# IADC_PCB_SCH.net
KiCad netlist of a schematic drawn in Altium Designer
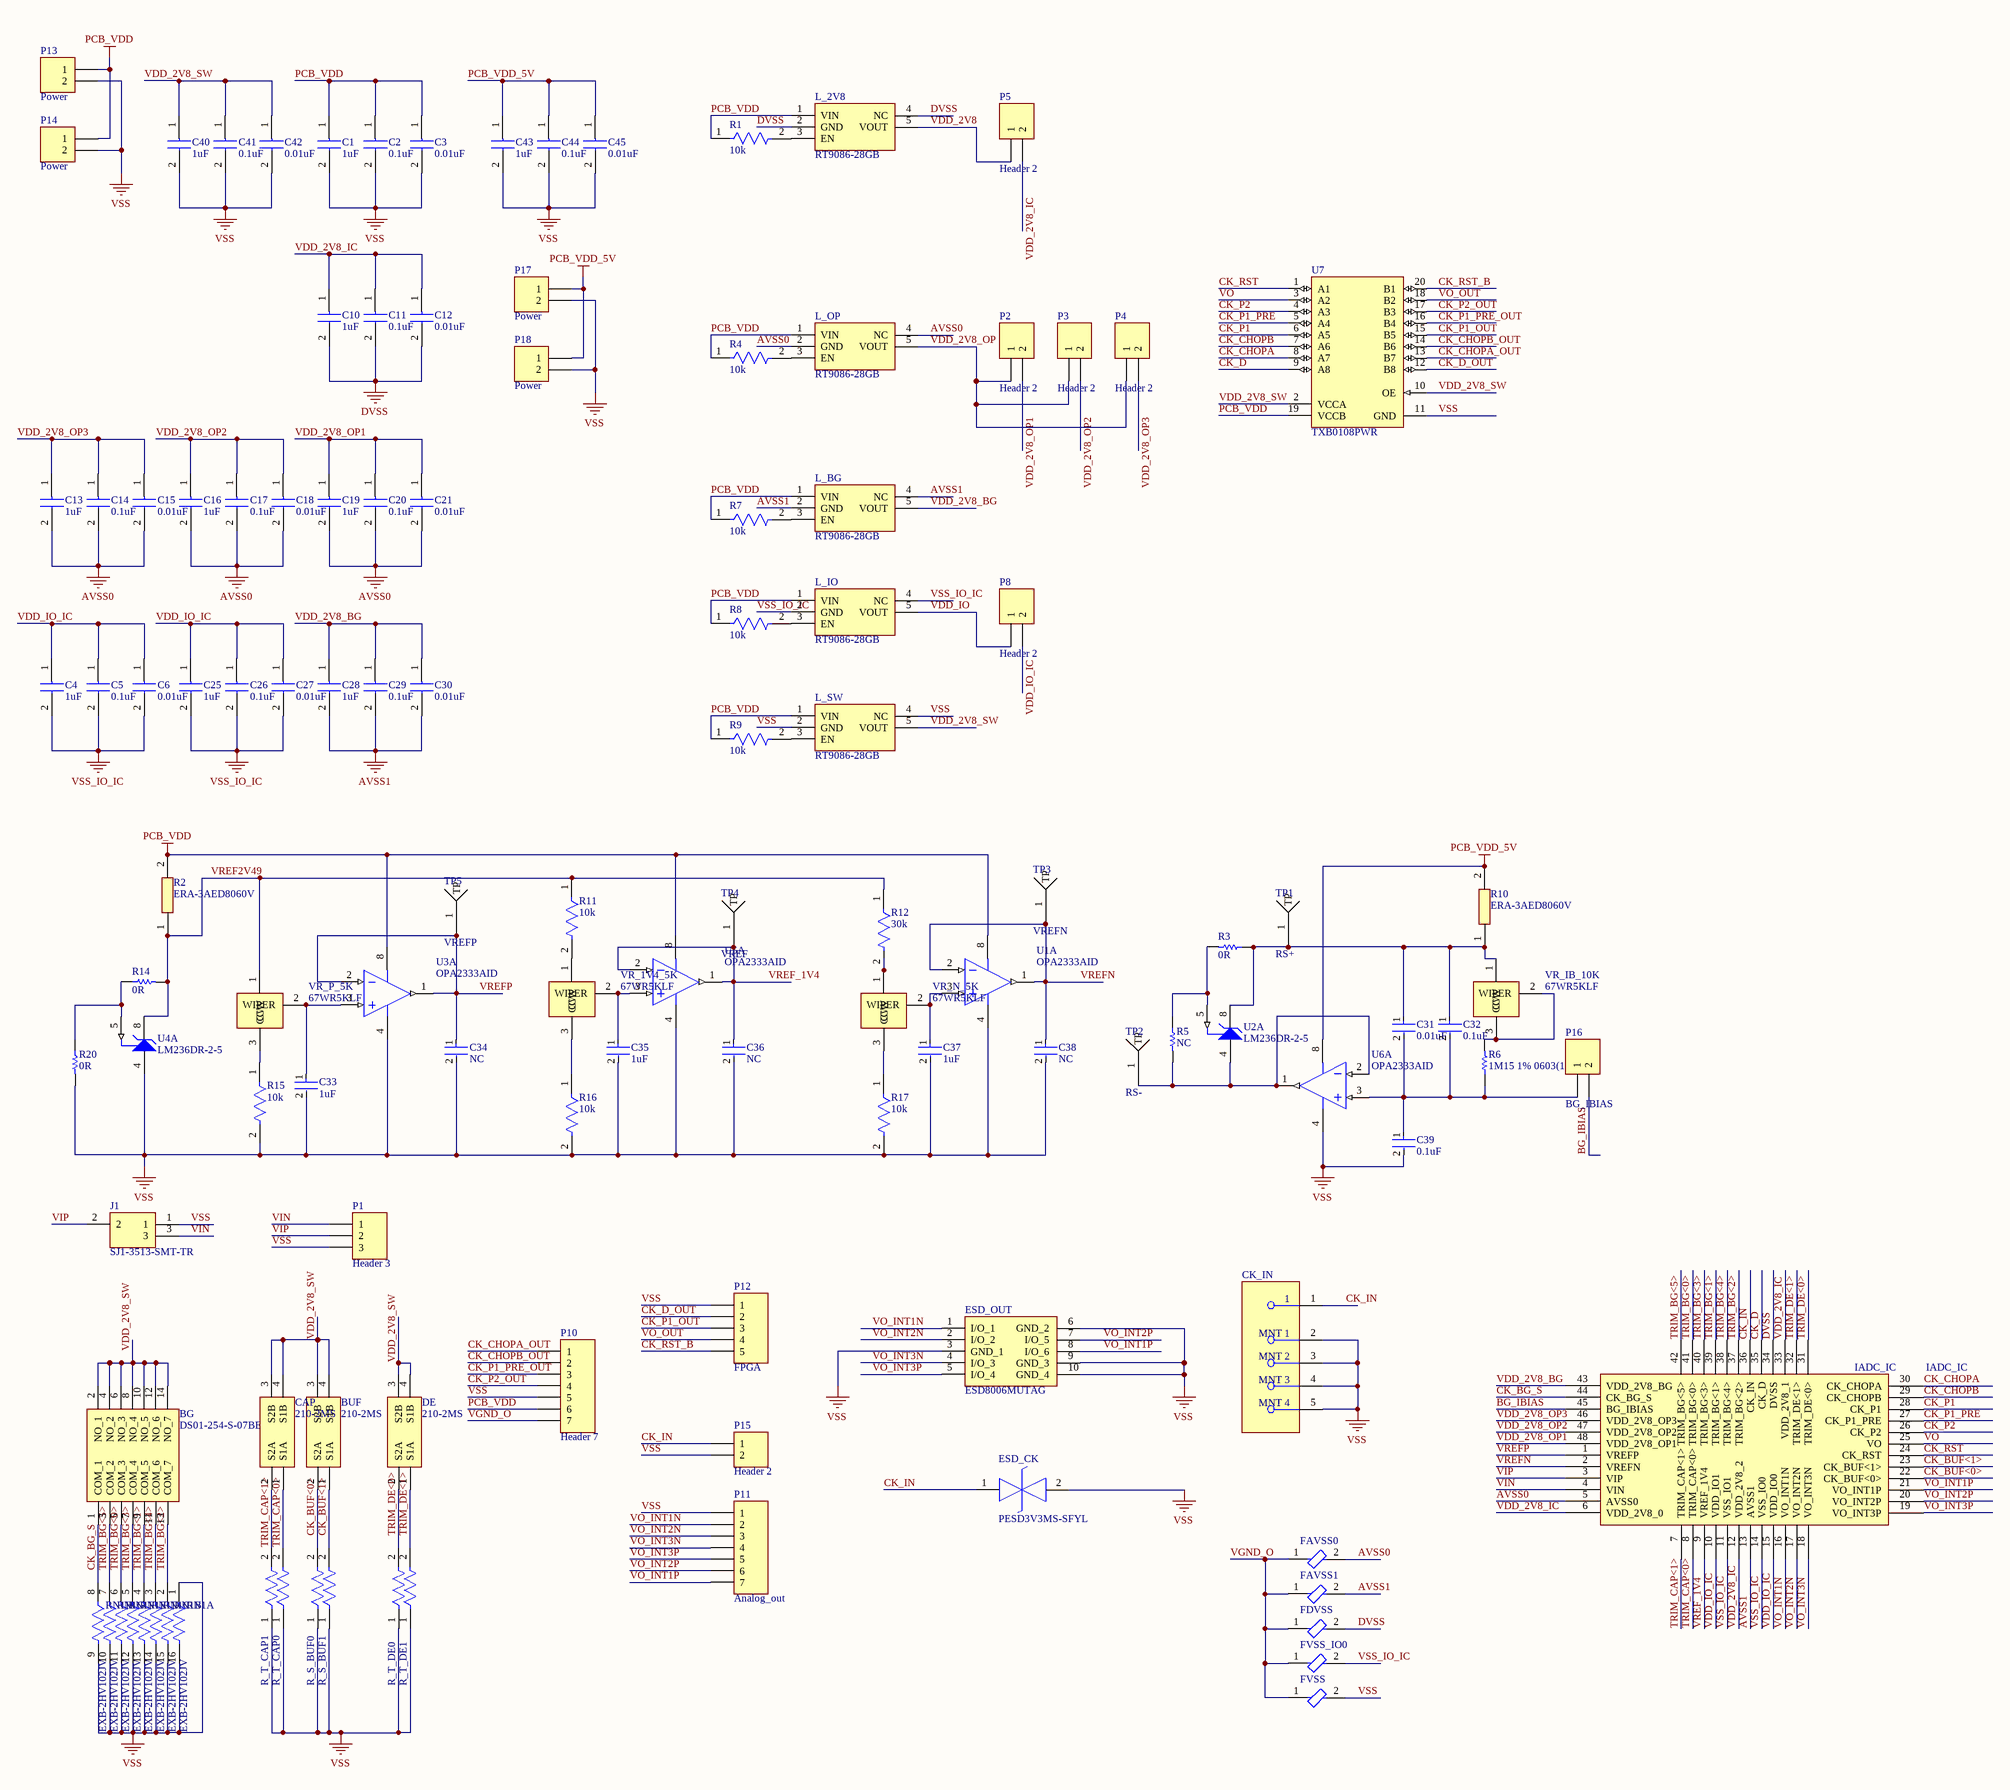
[diagram p0: IADC_PCB_SCH.SchDoc]

(export (version "E")
  (design (tool "Eeschema 10.0.6"))
  (components
    (comp (ref "BG")
      (value "DS01-254-S-07BE")
      (footprint "SamacSys:DS01254S07BE")
      (description "Switch")
      (fields (field (name "MOUSER PART NUMBER") "490-DS01-254-S-07BE"))
      (libsource (lib "Schlib2") (part "DS01-254-S-07BE"))
    )
    (comp (ref "BUF")
      (value "210-2MS")
      (footprint "SamacSys:DIP775W63P254L655H458Q4N")
      (description "Switch")
      (fields (field (name "MOUSER PART NUMBER") "774-2102MS"))
      (libsource (lib "Schlib2") (part "210-2MS"))
    )
    (comp (ref "C1")
      (value "1uF")
      (footprint "SamacSys:CAPC1608X95N")
      (description "多層陶瓷電容器MLCC - SMD/SMT 50V 1uF X7R 0603 10% HI CV")
      (fields
        (field (name "MANUFACTURER_PART_NUMBER") "CC0603KRX7R9BB105")
        (field (name "MOUSER PART NUMBER") "603-CC603KRX7R9BB105")
      )
      (libsource (lib "Schlib2") (part "CC0603KRX7R9BB105"))
    )
    (comp (ref "C2")
      (value "0.1uF")
      (footprint "SamacSys:CAPC1608X90N")
      (description "多層陶瓷電容器MLCC - SMD/SMT 25 V 0.1uF X7R 0603 10%")
      (fields
        (field (name "MANUFACTURER_PART_NUMBER") "CC0603KRX7R8BB104")
        (field (name "MOUSER PART NUMBER") "603-CC603KRX7R8BB104")
      )
      (libsource (lib "Schlib2") (part "CC0603KRX7R8BB104"))
    )
    (comp (ref "C3")
      (value "0.01uF")
      (footprint "SamacSys:CAPC1608X95N")
      (description "多層陶瓷電容器MLCC - SMD/SMT 25V 0.01uF X7R 0603 10%")
      (fields
        (field (name "MANUFACTURER_PART_NUMBER") "CC0603KRX7R9BB105")
        (field (name "MOUSER PART NUMBER") "603-CC603KRX7R9BB105")
      )
      (libsource (lib "Schlib2") (part "CC0603KRX7R9BB105_1"))
    )
    (comp (ref "C4")
      (value "1uF")
      (footprint "SamacSys:CAPC1608X95N")
      (description "多層陶瓷電容器MLCC - SMD/SMT 50V 1uF X7R 0603 10% HI CV")
      (fields
        (field (name "MANUFACTURER_PART_NUMBER") "CC0603KRX7R9BB105")
        (field (name "MOUSER PART NUMBER") "603-CC603KRX7R9BB105")
      )
      (libsource (lib "Schlib2") (part "CC0603KRX7R9BB105"))
    )
    (comp (ref "C5")
      (value "0.1uF")
      (footprint "SamacSys:CAPC1608X90N")
      (description "多層陶瓷電容器MLCC - SMD/SMT 25 V 0.1uF X7R 0603 10%")
      (fields
        (field (name "MANUFACTURER_PART_NUMBER") "CC0603KRX7R8BB104")
        (field (name "MOUSER PART NUMBER") "603-CC603KRX7R8BB104")
      )
      (libsource (lib "Schlib2") (part "CC0603KRX7R8BB104"))
    )
    (comp (ref "C6")
      (value "0.01uF")
      (footprint "SamacSys:CAPC1608X95N")
      (description "多層陶瓷電容器MLCC - SMD/SMT 25V 0.01uF X7R 0603 10%")
      (fields
        (field (name "MANUFACTURER_PART_NUMBER") "CC0603KRX7R9BB105")
        (field (name "MOUSER PART NUMBER") "603-CC603KRX7R9BB105")
      )
      (libsource (lib "Schlib2") (part "CC0603KRX7R9BB105_1"))
    )
    (comp (ref "C10")
      (value "1uF")
      (footprint "SamacSys:CAPC1608X95N")
      (description "多層陶瓷電容器MLCC - SMD/SMT 50V 1uF X7R 0603 10% HI CV")
      (fields
        (field (name "MANUFACTURER_PART_NUMBER") "CC0603KRX7R9BB105")
        (field (name "MOUSER PART NUMBER") "603-CC603KRX7R9BB105")
      )
      (libsource (lib "Schlib2") (part "CC0603KRX7R9BB105"))
    )
    (comp (ref "C11")
      (value "0.1uF")
      (footprint "SamacSys:CAPC1608X90N")
      (description "多層陶瓷電容器MLCC - SMD/SMT 25 V 0.1uF X7R 0603 10%")
      (fields
        (field (name "MANUFACTURER_PART_NUMBER") "CC0603KRX7R8BB104")
        (field (name "MOUSER PART NUMBER") "603-CC603KRX7R8BB104")
      )
      (libsource (lib "Schlib2") (part "CC0603KRX7R8BB104"))
    )
    (comp (ref "C12")
      (value "0.01uF")
      (footprint "SamacSys:CAPC1608X95N")
      (description "多層陶瓷電容器MLCC - SMD/SMT 25V 0.01uF X7R 0603 10%")
      (fields
        (field (name "MANUFACTURER_PART_NUMBER") "CC0603KRX7R9BB105")
        (field (name "MOUSER PART NUMBER") "603-CC603KRX7R9BB105")
      )
      (libsource (lib "Schlib2") (part "CC0603KRX7R9BB105_1"))
    )
    (comp (ref "C13")
      (value "1uF")
      (footprint "SamacSys:CAPC1608X95N")
      (description "多層陶瓷電容器MLCC - SMD/SMT 50V 1uF X7R 0603 10% HI CV")
      (fields
        (field (name "MANUFACTURER_PART_NUMBER") "CC0603KRX7R9BB105")
        (field (name "MOUSER PART NUMBER") "603-CC603KRX7R9BB105")
      )
      (libsource (lib "Schlib2") (part "CC0603KRX7R9BB105"))
    )
    (comp (ref "C14")
      (value "0.1uF")
      (footprint "SamacSys:CAPC1608X90N")
      (description "多層陶瓷電容器MLCC - SMD/SMT 25 V 0.1uF X7R 0603 10%")
      (fields
        (field (name "MANUFACTURER_PART_NUMBER") "CC0603KRX7R8BB104")
        (field (name "MOUSER PART NUMBER") "603-CC603KRX7R8BB104")
      )
      (libsource (lib "Schlib2") (part "CC0603KRX7R8BB104"))
    )
    (comp (ref "C15")
      (value "0.01uF")
      (footprint "SamacSys:CAPC1608X95N")
      (description "多層陶瓷電容器MLCC - SMD/SMT 25V 0.01uF X7R 0603 10%")
      (fields
        (field (name "MANUFACTURER_PART_NUMBER") "CC0603KRX7R9BB105")
        (field (name "MOUSER PART NUMBER") "603-CC603KRX7R9BB105")
      )
      (libsource (lib "Schlib2") (part "CC0603KRX7R9BB105_1"))
    )
    (comp (ref "C16")
      (value "1uF")
      (footprint "SamacSys:CAPC1608X95N")
      (description "多層陶瓷電容器MLCC - SMD/SMT 50V 1uF X7R 0603 10% HI CV")
      (fields
        (field (name "MANUFACTURER_PART_NUMBER") "CC0603KRX7R9BB105")
        (field (name "MOUSER PART NUMBER") "603-CC603KRX7R9BB105")
      )
      (libsource (lib "Schlib2") (part "CC0603KRX7R9BB105"))
    )
    (comp (ref "C17")
      (value "0.1uF")
      (footprint "SamacSys:CAPC1608X90N")
      (description "多層陶瓷電容器MLCC - SMD/SMT 25 V 0.1uF X7R 0603 10%")
      (fields
        (field (name "MANUFACTURER_PART_NUMBER") "CC0603KRX7R8BB104")
        (field (name "MOUSER PART NUMBER") "603-CC603KRX7R8BB104")
      )
      (libsource (lib "Schlib2") (part "CC0603KRX7R8BB104"))
    )
    (comp (ref "C18")
      (value "0.01uF")
      (footprint "SamacSys:CAPC1608X95N")
      (description "多層陶瓷電容器MLCC - SMD/SMT 25V 0.01uF X7R 0603 10%")
      (fields
        (field (name "MANUFACTURER_PART_NUMBER") "CC0603KRX7R9BB105")
        (field (name "MOUSER PART NUMBER") "603-CC603KRX7R9BB105")
      )
      (libsource (lib "Schlib2") (part "CC0603KRX7R9BB105_1"))
    )
    (comp (ref "C19")
      (value "1uF")
      (footprint "SamacSys:CAPC1608X95N")
      (description "多層陶瓷電容器MLCC - SMD/SMT 50V 1uF X7R 0603 10% HI CV")
      (fields
        (field (name "MANUFACTURER_PART_NUMBER") "CC0603KRX7R9BB105")
        (field (name "MOUSER PART NUMBER") "603-CC603KRX7R9BB105")
      )
      (libsource (lib "Schlib2") (part "CC0603KRX7R9BB105"))
    )
    (comp (ref "C20")
      (value "0.1uF")
      (footprint "SamacSys:CAPC1608X90N")
      (description "多層陶瓷電容器MLCC - SMD/SMT 25 V 0.1uF X7R 0603 10%")
      (fields
        (field (name "MANUFACTURER_PART_NUMBER") "CC0603KRX7R8BB104")
        (field (name "MOUSER PART NUMBER") "603-CC603KRX7R8BB104")
      )
      (libsource (lib "Schlib2") (part "CC0603KRX7R8BB104"))
    )
    (comp (ref "C21")
      (value "0.01uF")
      (footprint "SamacSys:CAPC1608X95N")
      (description "多層陶瓷電容器MLCC - SMD/SMT 25V 0.01uF X7R 0603 10%")
      (fields
        (field (name "MANUFACTURER_PART_NUMBER") "CC0603KRX7R9BB105")
        (field (name "MOUSER PART NUMBER") "603-CC603KRX7R9BB105")
      )
      (libsource (lib "Schlib2") (part "CC0603KRX7R9BB105_1"))
    )
    (comp (ref "C25")
      (value "1uF")
      (footprint "SamacSys:CAPC1608X95N")
      (description "多層陶瓷電容器MLCC - SMD/SMT 50V 1uF X7R 0603 10% HI CV")
      (fields
        (field (name "MANUFACTURER_PART_NUMBER") "CC0603KRX7R9BB105")
        (field (name "MOUSER PART NUMBER") "603-CC603KRX7R9BB105")
      )
      (libsource (lib "Schlib2") (part "CC0603KRX7R9BB105"))
    )
    (comp (ref "C26")
      (value "0.1uF")
      (footprint "SamacSys:CAPC1608X90N")
      (description "多層陶瓷電容器MLCC - SMD/SMT 25 V 0.1uF X7R 0603 10%")
      (fields
        (field (name "MANUFACTURER_PART_NUMBER") "CC0603KRX7R8BB104")
        (field (name "MOUSER PART NUMBER") "603-CC603KRX7R8BB104")
      )
      (libsource (lib "Schlib2") (part "CC0603KRX7R8BB104"))
    )
    (comp (ref "C27")
      (value "0.01uF")
      (footprint "SamacSys:CAPC1608X95N")
      (description "多層陶瓷電容器MLCC - SMD/SMT 25V 0.01uF X7R 0603 10%")
      (fields
        (field (name "MANUFACTURER_PART_NUMBER") "CC0603KRX7R9BB105")
        (field (name "MOUSER PART NUMBER") "603-CC603KRX7R9BB105")
      )
      (libsource (lib "Schlib2") (part "CC0603KRX7R9BB105_1"))
    )
    (comp (ref "C28")
      (value "1uF")
      (footprint "SamacSys:CAPC1608X95N")
      (description "多層陶瓷電容器MLCC - SMD/SMT 50V 1uF X7R 0603 10% HI CV")
      (fields
        (field (name "MANUFACTURER_PART_NUMBER") "CC0603KRX7R9BB105")
        (field (name "MOUSER PART NUMBER") "603-CC603KRX7R9BB105")
      )
      (libsource (lib "Schlib2") (part "CC0603KRX7R9BB105"))
    )
    (comp (ref "C29")
      (value "0.1uF")
      (footprint "SamacSys:CAPC1608X90N")
      (description "多層陶瓷電容器MLCC - SMD/SMT 25 V 0.1uF X7R 0603 10%")
      (fields
        (field (name "MANUFACTURER_PART_NUMBER") "CC0603KRX7R8BB104")
        (field (name "MOUSER PART NUMBER") "603-CC603KRX7R8BB104")
      )
      (libsource (lib "Schlib2") (part "CC0603KRX7R8BB104"))
    )
    (comp (ref "C30")
      (value "0.01uF")
      (footprint "SamacSys:CAPC1608X95N")
      (description "多層陶瓷電容器MLCC - SMD/SMT 25V 0.01uF X7R 0603 10%")
      (fields
        (field (name "MANUFACTURER_PART_NUMBER") "CC0603KRX7R9BB105")
        (field (name "MOUSER PART NUMBER") "603-CC603KRX7R9BB105")
      )
      (libsource (lib "Schlib2") (part "CC0603KRX7R9BB105_1"))
    )
    (comp (ref "C31")
      (value "0.01uF")
      (footprint "FP-CC0603-DA-MFG")
      (description "CAP CER 10000PF 50V X7R 0603")
      (fields (field (name "TOLERANCE") "0.1") (field (name "MANUFACTURER PART NUMBER") "CC0603KRX7R9BB103"))
      (libsource (lib "Altium Content Vault") (part "11868f565c42a9108669ba33697ecf6"))
    )
    (comp (ref "C32")
      (value "0.1uF")
      (footprint "FP-CC0603-DA-MFG")
      (description "CAP CER 0.1UF 50V X7R 0603")
      (fields (field (name "MANUFACTURER") "YAGEO") (field (name "VOLTAGE") "50 V"))
      (libsource (lib "Altium Content Vault") (part "11868f565c42a9108669ba33697ecf6"))
    )
    (comp (ref "C33")
      (value "1uF")
      (footprint "FP-CC0603-DA-MFG")
      (description "CAP CER 1UF 16V X7R 0603")
      (fields (field (name "TOLERANCE") "0.1") (field (name "MANUFACTURER") "YAGEO"))
      (libsource (lib "Altium Content Vault") (part "11868f565c42a9108669ba33697ecf6"))
    )
    (comp (ref "C34")
      (value "NC")
      (footprint "FP-CC0603-DA-MFG")
      (description "CAP CER 1UF 16V X7R 0603")
      (fields (field (name "TOLERANCE") "0.1") (field (name "MANUFACTURER") "YAGEO"))
      (libsource (lib "Altium Content Vault") (part "11868f565c42a9108669ba33697ecf6"))
    )
    (comp (ref "C35")
      (value "1uF")
      (footprint "FP-CC0603-DA-MFG")
      (description "CAP CER 1UF 16V X7R 0603")
      (fields (field (name "TOLERANCE") "0.1") (field (name "MANUFACTURER") "YAGEO"))
      (libsource (lib "Altium Content Vault") (part "11868f565c42a9108669ba33697ecf6"))
    )
    (comp (ref "C36")
      (value "NC")
      (footprint "FP-CC0603-DA-MFG")
      (description "CAP CER 1UF 16V X7R 0603")
      (fields (field (name "TOLERANCE") "0.1") (field (name "MANUFACTURER") "YAGEO"))
      (libsource (lib "Altium Content Vault") (part "11868f565c42a9108669ba33697ecf6"))
    )
    (comp (ref "C37")
      (value "1uF")
      (footprint "FP-CC0603-DA-MFG")
      (description "CAP CER 1UF 16V X7R 0603")
      (fields (field (name "TOLERANCE") "0.1") (field (name "MANUFACTURER") "YAGEO"))
      (libsource (lib "Altium Content Vault") (part "11868f565c42a9108669ba33697ecf6"))
    )
    (comp (ref "C38")
      (value "NC")
      (footprint "FP-CC0603-DA-MFG")
      (description "CAP CER 1UF 16V X7R 0603")
      (fields (field (name "TOLERANCE") "0.1") (field (name "MANUFACTURER") "YAGEO"))
      (libsource (lib "Altium Content Vault") (part "11868f565c42a9108669ba33697ecf6"))
    )
    (comp (ref "C39")
      (value "0.1uF")
      (footprint "FP-CC0603-DA-MFG")
      (description "CAP CER 0.1UF 50V X7R 0603")
      (fields (field (name "MANUFACTURER") "YAGEO") (field (name "VOLTAGE") "50 V"))
      (libsource (lib "Altium Content Vault") (part "11868f565c42a9108669ba33697ecf6"))
    )
    (comp (ref "C40")
      (value "1uF")
      (footprint "SamacSys:CAPC1608X95N")
      (description "多層陶瓷電容器MLCC - SMD/SMT 50V 1uF X7R 0603 10% HI CV")
      (fields
        (field (name "MANUFACTURER_PART_NUMBER") "CC0603KRX7R9BB105")
        (field (name "MOUSER PART NUMBER") "603-CC603KRX7R9BB105")
      )
      (libsource (lib "Schlib2") (part "CC0603KRX7R9BB105"))
    )
    (comp (ref "C41")
      (value "0.1uF")
      (footprint "SamacSys:CAPC1608X90N")
      (description "多層陶瓷電容器MLCC - SMD/SMT 25 V 0.1uF X7R 0603 10%")
      (fields
        (field (name "MANUFACTURER_PART_NUMBER") "CC0603KRX7R8BB104")
        (field (name "MOUSER PART NUMBER") "603-CC603KRX7R8BB104")
      )
      (libsource (lib "Schlib2") (part "CC0603KRX7R8BB104"))
    )
    (comp (ref "C42")
      (value "0.01uF")
      (footprint "SamacSys:CAPC1608X95N")
      (description "多層陶瓷電容器MLCC - SMD/SMT 25V 0.01uF X7R 0603 10%")
      (fields
        (field (name "MANUFACTURER_PART_NUMBER") "CC0603KRX7R9BB105")
        (field (name "MOUSER PART NUMBER") "603-CC603KRX7R9BB105")
      )
      (libsource (lib "Schlib2") (part "CC0603KRX7R9BB105_1"))
    )
    (comp (ref "C43")
      (value "1uF")
      (footprint "SamacSys:CAPC1608X95N")
      (description "多層陶瓷電容器MLCC - SMD/SMT 50V 1uF X7R 0603 10% HI CV")
      (fields
        (field (name "MANUFACTURER_PART_NUMBER") "CC0603KRX7R9BB105")
        (field (name "MOUSER PART NUMBER") "603-CC603KRX7R9BB105")
      )
      (libsource (lib "Schlib2") (part "CC0603KRX7R9BB105"))
    )
    (comp (ref "C44")
      (value "0.1uF")
      (footprint "SamacSys:CAPC1608X90N")
      (description "多層陶瓷電容器MLCC - SMD/SMT 25 V 0.1uF X7R 0603 10%")
      (fields
        (field (name "MANUFACTURER_PART_NUMBER") "CC0603KRX7R8BB104")
        (field (name "MOUSER PART NUMBER") "603-CC603KRX7R8BB104")
      )
      (libsource (lib "Schlib2") (part "CC0603KRX7R8BB104"))
    )
    (comp (ref "C45")
      (value "0.01uF")
      (footprint "SamacSys:CAPC1608X95N")
      (description "多層陶瓷電容器MLCC - SMD/SMT 25V 0.01uF X7R 0603 10%")
      (fields
        (field (name "MANUFACTURER_PART_NUMBER") "CC0603KRX7R9BB105")
        (field (name "MOUSER PART NUMBER") "603-CC603KRX7R9BB105")
      )
      (libsource (lib "Schlib2") (part "CC0603KRX7R9BB105_1"))
    )
    (comp (ref "CAP")
      (value "210-2MS")
      (footprint "SamacSys:DIP775W63P254L655H458Q4N")
      (description "Switch")
      (fields (field (name "MOUSER PART NUMBER") "774-2102MS"))
      (libsource (lib "Schlib2") (part "210-2MS"))
    )
    (comp (ref "CK_IN")
      (value "221790-1")
      (footprint "FP-221790-1-MFG")
      (description "CONN SMA JACK R/A 50 OHM PCB")
      (fields
        (field (name "OCTOPART") "https://octopart.com/2217901-te+connectivity+%2F+amp-3339836")
        (field (name "MANUFACTURER") "TE Connectivity / AMP")
      )
      (libsource (lib "Altium Content Vault") (part "c65b8a639cdaef1819ea20b5466f8fa"))
    )
    (comp (ref "DE")
      (value "210-2MS")
      (footprint "SamacSys:DIP775W63P254L655H458Q4N")
      (description "Switch")
      (fields (field (name "MOUSER PART NUMBER") "774-2102MS"))
      (libsource (lib "Schlib2") (part "210-2MS"))
    )
    (comp (ref "ESD_CK")
      (value "PESD3V3MS-SFYL")
      (footprint "SamacSys:PMEG3005AESFYL")
      (description "Diode ESD (Bi-directional)")
      (fields (field (name "MOUSER PART NUMBER") "771-PESD3V3MS-SFYL"))
      (libsource (lib "Schlib2") (part "PESD3V3MS-SFYL"))
    )
    (comp (ref "ESD_OUT")
      (value "ESD8006MUTAG")
      (footprint "SamacSys:ESD8006MUTAG")
      (description "Integrated Circuit")
      (fields (field (name "MOUSER PART NUMBER") "863-ESD8006MUTAG"))
      (libsource (lib "Schlib2") (part "ESD8006MUTAG"))
    )
    (comp (ref "FAVSS0")
      (value "742792609")
      (footprint "FP-742792609-MFG")
      (description "FERRITE BEAD 30 OHM 0603 1LN")
      (fields (field (name "TOLERANCE") "25%"))
      (libsource (lib "Altium Content Vault") (part "5f30dd21d616792df468990f7003faa"))
    )
    (comp (ref "FAVSS1")
      (value "742792609")
      (footprint "FP-742792609-MFG")
      (description "FERRITE BEAD 30 OHM 0603 1LN")
      (fields (field (name "TOLERANCE") "25%"))
      (libsource (lib "Altium Content Vault") (part "5f30dd21d616792df468990f7003faa"))
    )
    (comp (ref "FDVSS")
      (value "742792609")
      (footprint "FP-742792609-MFG")
      (description "FERRITE BEAD 30 OHM 0603 1LN")
      (fields (field (name "TOLERANCE") "25%"))
      (libsource (lib "Altium Content Vault") (part "5f30dd21d616792df468990f7003faa"))
    )
    (comp (ref "FVSS")
      (value "742792609")
      (footprint "FP-742792609-MFG")
      (description "FERRITE BEAD 30 OHM 0603 1LN")
      (fields (field (name "TOLERANCE") "25%"))
      (libsource (lib "Altium Content Vault") (part "5f30dd21d616792df468990f7003faa"))
    )
    (comp (ref "FVSS_IO0")
      (value "742792609")
      (footprint "FP-742792609-MFG")
      (description "FERRITE BEAD 30 OHM 0603 1LN")
      (fields (field (name "TOLERANCE") "25%"))
      (libsource (lib "Altium Content Vault") (part "5f30dd21d616792df468990f7003faa"))
    )
    (comp (ref "IADC_IC")
      (value "IADC_IC")
      (footprint "PcbLib1:SB48 (DIP48)")
      (libsource (lib "Schlib2") (part "IADC_IC"))
    )
    (comp (ref "J1")
      (value "SJ1-3513-SMT-TR")
      (footprint "SamacSys:SJ13513SMTTR")
      (description "Connector")
      (fields (field (name "MOUSER PART NUMBER") "490-SJ1-3513-SMT-TR"))
      (libsource (lib "Schlib2") (part "SJ1-3513-SMT-TR"))
    )
    (comp (ref "L_2V8")
      (value "RT9086-28GB")
      (footprint "SamacSys:SOT94P279X130-5N")
      (description "Integrated Circuit")
      (libsource (lib "Schlib2") (part "RT9086-28GB"))
    )
    (comp (ref "L_BG")
      (value "RT9086-28GB")
      (footprint "SamacSys:SOT94P279X130-5N")
      (description "Integrated Circuit")
      (libsource (lib "Schlib2") (part "RT9086-28GB"))
    )
    (comp (ref "L_IO")
      (value "RT9086-28GB")
      (footprint "SamacSys:SOT94P279X130-5N")
      (description "Integrated Circuit")
      (libsource (lib "Schlib2") (part "RT9086-28GB"))
    )
    (comp (ref "L_OP")
      (value "RT9086-28GB")
      (footprint "SamacSys:SOT94P279X130-5N")
      (description "Integrated Circuit")
      (libsource (lib "Schlib2") (part "RT9086-28GB"))
    )
    (comp (ref "L_SW")
      (value "RT9086-28GB")
      (footprint "SamacSys:SOT94P279X130-5N")
      (description "Integrated Circuit")
      (libsource (lib "Schlib2") (part "RT9086-28GB"))
    )
    (comp (ref "P1")
      (value "Header 3")
      (footprint "HDR1X3")
      (description "Header, 3-Pin")
      (fields (field (name "PUBLISHER") "Altium Limited"))
      (libsource (lib "Miscellaneous Connectors") (part "Header 3"))
    )
    (comp (ref "P2")
      (value "Header 2")
      (footprint "HDR1X2")
      (description "Header, 2-Pin")
      (fields (field (name "PUBLISHER") "Altium Limited"))
      (libsource (lib "") (part "Header 2_1"))
    )
    (comp (ref "P3")
      (value "Header 2")
      (footprint "HDR1X2")
      (description "Header, 2-Pin")
      (fields (field (name "PUBLISHER") "Altium Limited"))
      (libsource (lib "") (part "Header 2_1"))
    )
    (comp (ref "P4")
      (value "Header 2")
      (footprint "HDR1X2")
      (description "Header, 2-Pin")
      (fields (field (name "PUBLISHER") "Altium Limited"))
      (libsource (lib "") (part "Header 2_1"))
    )
    (comp (ref "P5")
      (value "Header 2")
      (footprint "HDR1X2")
      (description "Header, 2-Pin")
      (fields (field (name "PUBLISHER") "Altium Limited"))
      (libsource (lib "") (part "Header 2_1"))
    )
    (comp (ref "P8")
      (value "Header 2")
      (footprint "HDR1X2")
      (description "Header, 2-Pin")
      (fields (field (name "PUBLISHER") "Altium Limited"))
      (libsource (lib "") (part "Header 2_1"))
    )
    (comp (ref "P10")
      (value "Header 7")
      (footprint "HDR1X7")
      (description "Header, 7-Pin")
      (fields (field (name "PUBLISHER") "Altium Limited"))
      (libsource (lib "Miscellaneous Connectors") (part "Header 7"))
    )
    (comp (ref "P11")
      (value "Analog_out")
      (footprint "HDR1X7")
      (description "Header, 7-Pin")
      (fields (field (name "PUBLISHER") "Altium Limited"))
      (libsource (lib "Miscellaneous Connectors") (part "Header 7"))
    )
    (comp (ref "P12")
      (value "FPGA")
      (footprint "HDR1X5")
      (description "Header, 5-Pin")
      (fields (field (name "PUBLISHER") "Altium Limited"))
      (libsource (lib "Miscellaneous Connectors") (part "Header 5"))
    )
    (comp (ref "P13")
      (value "Power")
      (footprint "HDR1X2")
      (description "Header, 2-Pin")
      (fields (field (name "PUBLISHER") "Altium Limited"))
      (libsource (lib "") (part "Header 2_2"))
    )
    (comp (ref "P14")
      (value "Power")
      (footprint "HDR1X2")
      (description "Header, 2-Pin")
      (fields (field (name "PUBLISHER") "Altium Limited"))
      (libsource (lib "") (part "Header 2_2"))
    )
    (comp (ref "P15")
      (value "Header 2")
      (footprint "HDR1X2")
      (description "Header, 2-Pin")
      (fields (field (name "PUBLISHER") "Altium Limited"))
      (libsource (lib "Miscellaneous Connectors") (part "Header 2"))
    )
    (comp (ref "P16")
      (value "BG_IBIAS")
      (footprint "HDR1X2")
      (description "Header, 2-Pin")
      (fields (field (name "PUBLISHER") "Altium Limited"))
      (libsource (lib "") (part "Header 2_1"))
    )
    (comp (ref "P17")
      (value "Power")
      (footprint "HDR1X2")
      (description "Header, 2-Pin")
      (fields (field (name "PUBLISHER") "Altium Limited"))
      (libsource (lib "") (part "Header 2_2"))
    )
    (comp (ref "P18")
      (value "Power")
      (footprint "HDR1X2")
      (description "Header, 2-Pin")
      (fields (field (name "PUBLISHER") "Altium Limited"))
      (libsource (lib "") (part "Header 2_2"))
    )
    (comp (ref "R1")
      (value "10k")
      (footprint "FP-RC0603-0_55-IPC_C")
      (description "RES 10K OHM 1% 1/10W 0603")
      (fields (field (name "TOLERANCE") "1%"))
      (libsource (lib "Altium Content Vault") (part "1029c3af85768c4190bb7ad29bc67b5"))
    )
    (comp (ref "R2")
      (value "ERA-3AED8060V")
      (footprint "SamacSys:ERA3AEB101V")
      (description "Resistor")
      (fields (field (name "MOUSER PART NUMBER") "667-ERA-3AED8060V"))
      (libsource (lib "Schlib2") (part "ERA-3AED8060V"))
    )
    (comp (ref "R3")
      (value "0R")
      (footprint "RESC1608X55X25ML10T15")
      (description "Chip Resistor, 0 Ohm, +/- 5%, 0.1 W, -55 to 155 degC, 0603 (1608 Metric), RoHS, Tape and Reel")
      (fields (field (name "TOLERANCE") "5%") (field (name "MANUFACTURER") "Yageo"))
      (libsource (lib "Altium Content Vault") (part "RES-2"))
    )
    (comp (ref "R4")
      (value "10k")
      (footprint "FP-RC0603-0_55-IPC_C")
      (description "RES 10K OHM 1% 1/10W 0603")
      (fields (field (name "TOLERANCE") "1%"))
      (libsource (lib "Altium Content Vault") (part "1029c3af85768c4190bb7ad29bc67b5"))
    )
    (comp (ref "R5")
      (value "NC")
      (footprint "RESC1608X55X25ML10T15")
      (description "Chip Resistor, 0 Ohm, +/- 5%, 0.1 W, -55 to 155 degC, 0603 (1608 Metric), RoHS, Tape and Reel")
      (fields (field (name "TOLERANCE") "5%") (field (name "MANUFACTURER") "Yageo"))
      (libsource (lib "Altium Content Vault") (part "RES-2"))
    )
    (comp (ref "R6")
      (value "1M15 1% 0603(1608)")
      (footprint "RESC0603(1608)_N")
      (description "1M15 0.1W 1% 0603 (1608 Metric)  SMD")
      (fields (field (name "POWER") "0.1 W") (field (name "TOLERANCE") "1 %"))
      (libsource (lib "Altium Content Vault") (part "RES"))
    )
    (comp (ref "R7")
      (value "10k")
      (footprint "FP-RC0603-0_55-IPC_C")
      (description "RES 10K OHM 1% 1/10W 0603")
      (fields (field (name "TOLERANCE") "1%"))
      (libsource (lib "Altium Content Vault") (part "1029c3af85768c4190bb7ad29bc67b5"))
    )
    (comp (ref "R8")
      (value "10k")
      (footprint "FP-RC0603-0_55-IPC_C")
      (description "RES 10K OHM 1% 1/10W 0603")
      (fields (field (name "TOLERANCE") "1%"))
      (libsource (lib "Altium Content Vault") (part "1029c3af85768c4190bb7ad29bc67b5"))
    )
    (comp (ref "R9")
      (value "10k")
      (footprint "FP-RC0603-0_55-IPC_C")
      (description "RES 10K OHM 1% 1/10W 0603")
      (fields (field (name "TOLERANCE") "1%"))
      (libsource (lib "Altium Content Vault") (part "1029c3af85768c4190bb7ad29bc67b5"))
    )
    (comp (ref "R10")
      (value "ERA-3AED8060V")
      (footprint "SamacSys:ERA3AEB101V")
      (description "Resistor")
      (fields (field (name "MOUSER PART NUMBER") "667-ERA-3AED8060V"))
      (libsource (lib "Schlib2") (part "ERA-3AED8060V"))
    )
    (comp (ref "R11")
      (value "10k")
      (footprint "FP-RC0603-0_55-MFG")
      (description "RES 10K OHM 1% 1/10W 0603")
      (fields (field (name "TOLERANCE") "1%"))
      (libsource (lib "Altium Content Vault") (part "1029c3af85768c4190bb7ad29bc67b5"))
    )
    (comp (ref "R12")
      (value "30k")
      (footprint "FP-RC0603-0_55-MFG")
      (description "RES 10K OHM 1% 1/10W 0603")
      (fields (field (name "TOLERANCE") "1%"))
      (libsource (lib "Altium Content Vault") (part "1029c3af85768c4190bb7ad29bc67b5"))
    )
    (comp (ref "R14")
      (value "0R")
      (footprint "RESC1608X55X25ML10T15")
      (description "Chip Resistor, 0 Ohm, +/- 5%, 0.1 W, -55 to 155 degC, 0603 (1608 Metric), RoHS, Tape and Reel")
      (fields (field (name "TOLERANCE") "5%") (field (name "MANUFACTURER") "Yageo"))
      (libsource (lib "Altium Content Vault") (part "RES-2"))
    )
    (comp (ref "R15")
      (value "10k")
      (footprint "FP-RC0603-0_55-MFG")
      (description "RES 10K OHM 1% 1/10W 0603")
      (fields (field (name "TOLERANCE") "1%"))
      (libsource (lib "Altium Content Vault") (part "1029c3af85768c4190bb7ad29bc67b5"))
    )
    (comp (ref "R16")
      (value "10k")
      (footprint "FP-RC0603-0_55-MFG")
      (description "RES 10K OHM 1% 1/10W 0603")
      (fields (field (name "TOLERANCE") "1%"))
      (libsource (lib "Altium Content Vault") (part "1029c3af85768c4190bb7ad29bc67b5"))
    )
    (comp (ref "R17")
      (value "10k")
      (footprint "FP-RC0603-0_55-MFG")
      (description "RES 10K OHM 1% 1/10W 0603")
      (fields (field (name "TOLERANCE") "1%"))
      (libsource (lib "Altium Content Vault") (part "1029c3af85768c4190bb7ad29bc67b5"))
    )
    (comp (ref "R20")
      (value "0R")
      (footprint "RESC1608X55X25ML10T15")
      (description "Chip Resistor, 0 Ohm, +/- 5%, 0.1 W, -55 to 155 degC, 0603 (1608 Metric), RoHS, Tape and Reel")
      (fields (field (name "TOLERANCE") "5%") (field (name "MANUFACTURER") "Yageo"))
      (libsource (lib "Altium Content Vault") (part "RES-2"))
    )
    (comp (ref "RN1")
      (value "EXB-2HV102JV")
      (footprint "FP-EXB2HV-MFG")
      (description "RES ARRAY 8 RES 1K OHM 1506")
      (fields
        (field (name "MANUFACTURER") "Panasonic")
        (field (name "OCTOPART") "https://octopart.com/exb-2hv102jv-panasonic-55561305")
      )
      (libsource (lib "Altium Content Vault") (part "eca46332945381b58ca122c3d0818be"))
    )
    (comp (ref "R_S_BUF0")
      (value "RT0603BRD071KL")
      (footprint "FP-RT0603-MFG")
      (description "RES SMD 1K OHM 0.1% 1/10W 0603")
      (fields (field (name "MANUFACTURER") "Yageo") (field (name "TOLERANCE") "0.1%"))
      (libsource (lib "Altium Content Vault") (part "1029c3af85768c4190bb7ad29bc67b5"))
    )
    (comp (ref "R_S_BUF1")
      (value "RT0603BRD071KL")
      (footprint "FP-RT0603-MFG")
      (description "RES SMD 1K OHM 0.1% 1/10W 0603")
      (fields (field (name "MANUFACTURER") "Yageo") (field (name "TOLERANCE") "0.1%"))
      (libsource (lib "Altium Content Vault") (part "1029c3af85768c4190bb7ad29bc67b5"))
    )
    (comp (ref "R_T_CAP0")
      (value "RT0603BRD071KL")
      (footprint "FP-RT0603-MFG")
      (description "RES SMD 1K OHM 0.1% 1/10W 0603")
      (fields (field (name "MANUFACTURER") "Yageo") (field (name "TOLERANCE") "0.1%"))
      (libsource (lib "Altium Content Vault") (part "1029c3af85768c4190bb7ad29bc67b5"))
    )
    (comp (ref "R_T_CAP1")
      (value "RT0603BRD071KL")
      (footprint "FP-RT0603-MFG")
      (description "RES SMD 1K OHM 0.1% 1/10W 0603")
      (fields (field (name "MANUFACTURER") "Yageo") (field (name "TOLERANCE") "0.1%"))
      (libsource (lib "Altium Content Vault") (part "1029c3af85768c4190bb7ad29bc67b5"))
    )
    (comp (ref "R_T_DE0")
      (value "RT0603BRD071KL")
      (footprint "FP-RT0603-MFG")
      (description "RES SMD 1K OHM 0.1% 1/10W 0603")
      (fields (field (name "MANUFACTURER") "Yageo") (field (name "TOLERANCE") "0.1%"))
      (libsource (lib "Altium Content Vault") (part "1029c3af85768c4190bb7ad29bc67b5"))
    )
    (comp (ref "R_T_DE1")
      (value "RT0603BRD071KL")
      (footprint "FP-RT0603-MFG")
      (description "RES SMD 1K OHM 0.1% 1/10W 0603")
      (fields (field (name "MANUFACTURER") "Yageo") (field (name "TOLERANCE") "0.1%"))
      (libsource (lib "Altium Content Vault") (part "1029c3af85768c4190bb7ad29bc67b5"))
    )
    (comp (ref "TP1") (value "RS+") (footprint "PcbLib1:TEST_POINT") (libsource (lib "Schlib2") (part "TP")))
    (comp (ref "TP2") (value "RS-") (footprint "PcbLib1:TEST_POINT") (libsource (lib "Schlib2") (part "TP")))
    (comp (ref "TP3")
      (value "VREFN")
      (footprint "PcbLib1:TEST_POINT")
      (libsource (lib "Schlib2") (part "TP"))
    )
    (comp (ref "TP4") (value "VREF") (footprint "PcbLib1:TEST_POINT") (libsource (lib "Schlib2") (part "TP")))
    (comp (ref "TP5")
      (value "VREFP")
      (footprint "PcbLib1:TEST_POINT")
      (libsource (lib "Schlib2") (part "TP"))
    )
    (comp (ref "U1")
      (value "OPA2333AID")
      (footprint "D0008A_L")
      (fields (field (name "MANUFACTURER") "Texas Instruments"))
      (libsource (lib "Altium Content Vault") (part "TI-OPA-8_2"))
    )
    (comp (ref "U2")
      (value "LM236DR-2-5")
      (footprint "D0008A_M")
      (fields (field (name "MANUFACTURER") "Texas Instruments"))
      (libsource (lib "Altium Content Vault") (part "TI-LM236-2_5D8"))
    )
    (comp (ref "U3")
      (value "OPA2333AID")
      (footprint "D0008A_L")
      (fields (field (name "MANUFACTURER") "Texas Instruments"))
      (libsource (lib "Altium Content Vault") (part "TI-OPA-8_2"))
    )
    (comp (ref "U4")
      (value "LM236DR-2-5")
      (footprint "D0008A_M")
      (fields (field (name "MANUFACTURER") "Texas Instruments"))
      (libsource (lib "Altium Content Vault") (part "TI-LM236-2_5D8"))
    )
    (comp (ref "U5")
      (value "OPA2333AID")
      (footprint "D0008A_L")
      (fields (field (name "MANUFACTURER") "Texas Instruments"))
      (libsource (lib "Altium Content Vault") (part "TI-OPA-8_2"))
    )
    (comp (ref "U6")
      (value "OPA2333AID")
      (footprint "D0008A_L")
      (fields (field (name "MANUFACTURER") "Texas Instruments"))
      (libsource (lib "Altium Content Vault") (part "TI-OPA-8_2"))
    )
    (comp (ref "U7")
      (value "TXB0108PWR")
      (footprint "PW0020A_L")
      (fields (field (name "MANUFACTURER") "Texas Instruments"))
      (libsource (lib "Altium Content Vault") (part "TI-TXB0108-PW-20"))
    )
    (comp (ref "VR_1V4_5K")
      (value "67WR5KLF")
      (footprint "SamacSys:67WR5KLF")
      (description "Variable Resistor 5K")
      (fields (field (name "MOUSER PART NUMBER") "858-67WR5KLF"))
      (libsource (lib "Schlib2") (part "67WR5KLF"))
    )
    (comp (ref "VR_IB_10K")
      (value "67WR5KLF")
      (footprint "SamacSys:67WR5KLF")
      (description "Variable Resistor 10K")
      (fields (field (name "MOUSER PART NUMBER") "858-67WR5KLF"))
      (libsource (lib "Schlib2") (part "67WR5KLF"))
    )
    (comp (ref "VR_N_5K")
      (value "67WR5KLF")
      (footprint "SamacSys:67WR5KLF")
      (description "Variable Resistor 5K")
      (fields (field (name "MOUSER PART NUMBER") "858-67WR5KLF"))
      (libsource (lib "Schlib2") (part "67WR5KLF"))
    )
    (comp (ref "VR_P_5K")
      (value "67WR5KLF")
      (footprint "SamacSys:67WR5KLF")
      (description "Variable Resistor 5K")
      (fields (field (name "MOUSER PART NUMBER") "858-67WR5KLF"))
      (libsource (lib "Schlib2") (part "67WR5KLF"))
    )
  )
  (nets
    (net (code "1") (name "/BG_IBIAS") (class "Default")
      (node (ref "IADC_IC") (pin "45") (pinfunction "BG_IBIAS_45") (pintype "passive"))
      (node (ref "P16") (pin "2") (pinfunction "2_2") (pintype "passive"))
    )
    (net (code "2") (name "/CK_BG_S") (class "Default")
      (node (ref "BG") (pin "1") (pinfunction "COM_1_1") (pintype "passive"))
      (node (ref "IADC_IC") (pin "44") (pinfunction "CK_BG_S_44") (pintype "passive"))
      (node (ref "RN1") (pin "8") (pinfunction "8_8") (pintype "passive"))
    )
    (net (code "3") (name "/CK_BUF<0>") (class "Default")
      (node (ref "BUF") (pin "2") (pinfunction "S2A_2") (pintype "passive"))
      (node (ref "IADC_IC") (pin "22") (pinfunction "CK_BUF<0>_22") (pintype "passive"))
      (node (ref "R_S_BUF0") (pin "2") (pinfunction "2_2") (pintype "passive"))
    )
    (net (code "4") (name "/CK_BUF<1>") (class "Default")
      (node (ref "BUF") (pin "1") (pinfunction "S1A_1") (pintype "passive"))
      (node (ref "IADC_IC") (pin "23") (pinfunction "CK_BUF<1>_23") (pintype "passive"))
      (node (ref "R_S_BUF1") (pin "2") (pinfunction "2_2") (pintype "passive"))
    )
    (net (code "5") (name "/CK_CHOPA") (class "Default")
      (node (ref "IADC_IC") (pin "30") (pinfunction "CK_CHOPA_30") (pintype "passive"))
      (node (ref "U7") (pin "8") (pinfunction "A7_8") (pintype "bidirectional"))
    )
    (net (code "6") (name "/CK_CHOPA_OUT") (class "Default")
      (node (ref "P10") (pin "1") (pinfunction "1_1") (pintype "passive"))
      (node (ref "U7") (pin "13") (pinfunction "B7_13") (pintype "bidirectional"))
    )
    (net (code "7") (name "/CK_CHOPB") (class "Default")
      (node (ref "IADC_IC") (pin "29") (pinfunction "CK_CHOPB_29") (pintype "passive"))
      (node (ref "U7") (pin "7") (pinfunction "A6_7") (pintype "bidirectional"))
    )
    (net (code "8") (name "/CK_CHOPB_OUT") (class "Default")
      (node (ref "P10") (pin "2") (pinfunction "2_2") (pintype "passive"))
      (node (ref "U7") (pin "14") (pinfunction "B6_14") (pintype "bidirectional"))
    )
    (net (code "9") (name "/CK_D") (class "Default")
      (node (ref "IADC_IC") (pin "35") (pinfunction "CK_D_35") (pintype "passive"))
      (node (ref "U7") (pin "9") (pinfunction "A8_9") (pintype "bidirectional"))
    )
    (net (code "10") (name "/CK_D_OUT") (class "Default")
      (node (ref "P12") (pin "2") (pinfunction "2_2") (pintype "passive"))
      (node (ref "U7") (pin "12") (pinfunction "B8_12") (pintype "bidirectional"))
    )
    (net (code "11") (name "/CK_IN") (class "Default")
      (node (ref "CK_IN") (pin "1") (pinfunction "1_1") (pintype "passive"))
      (node (ref "ESD_CK") (pin "1") (pinfunction "K1_1") (pintype "passive"))
      (node (ref "IADC_IC") (pin "36") (pinfunction "CK_IN_36") (pintype "passive"))
      (node (ref "P15") (pin "1") (pinfunction "1_1") (pintype "passive"))
    )
    (net (code "12") (name "/CK_P1") (class "Default")
      (node (ref "IADC_IC") (pin "28") (pinfunction "CK_P1_28") (pintype "passive"))
      (node (ref "U7") (pin "6") (pinfunction "A5_6") (pintype "bidirectional"))
    )
    (net (code "13") (name "/CK_P1_OUT") (class "Default")
      (node (ref "P12") (pin "3") (pinfunction "3_3") (pintype "passive"))
      (node (ref "U7") (pin "15") (pinfunction "B5_15") (pintype "bidirectional"))
    )
    (net (code "14") (name "/CK_P1_PRE") (class "Default")
      (node (ref "IADC_IC") (pin "27") (pinfunction "CK_P1_PRE_27") (pintype "passive"))
      (node (ref "U7") (pin "5") (pinfunction "A4_5") (pintype "bidirectional"))
    )
    (net (code "15") (name "/CK_P1_PRE_OUT") (class "Default")
      (node (ref "P10") (pin "3") (pinfunction "3_3") (pintype "passive"))
      (node (ref "U7") (pin "16") (pinfunction "B4_16") (pintype "bidirectional"))
    )
    (net (code "16") (name "/CK_P2") (class "Default")
      (node (ref "IADC_IC") (pin "26") (pinfunction "CK_P2_26") (pintype "passive"))
      (node (ref "U7") (pin "4") (pinfunction "A3_4") (pintype "bidirectional"))
    )
    (net (code "17") (name "/CK_P2_OUT") (class "Default")
      (node (ref "P10") (pin "4") (pinfunction "4_4") (pintype "passive"))
      (node (ref "U7") (pin "17") (pinfunction "B3_17") (pintype "bidirectional"))
    )
    (net (code "18") (name "/CK_RST") (class "Default")
      (node (ref "IADC_IC") (pin "24") (pinfunction "CK_RST_24") (pintype "passive"))
      (node (ref "U7") (pin "1") (pinfunction "A1_1") (pintype "bidirectional"))
    )
    (net (code "19") (name "/CK_RST_B") (class "Default")
      (node (ref "P12") (pin "5") (pinfunction "5_5") (pintype "passive"))
      (node (ref "U7") (pin "20") (pinfunction "B1_20") (pintype "bidirectional"))
    )
    (net (code "20") (name "/TRIM_BG<0>") (class "Default")
      (node (ref "BG") (pin "5") (pinfunction "COM_3_5") (pintype "passive"))
      (node (ref "IADC_IC") (pin "41") (pinfunction "TRIM_BG<0>_41") (pintype "passive"))
      (node (ref "RN1") (pin "6") (pinfunction "6_6") (pintype "passive"))
    )
    (net (code "21") (name "/TRIM_BG<1>") (class "Default")
      (node (ref "BG") (pin "9") (pinfunction "COM_5_9") (pintype "passive"))
      (node (ref "IADC_IC") (pin "39") (pinfunction "TRIM_BG<1>_39") (pintype "passive"))
      (node (ref "RN1") (pin "4") (pinfunction "4_4") (pintype "passive"))
    )
    (net (code "22") (name "/TRIM_BG<2>") (class "Default")
      (node (ref "BG") (pin "13") (pinfunction "COM_7_13") (pintype "passive"))
      (node (ref "IADC_IC") (pin "37") (pinfunction "TRIM_BG<2>_37") (pintype "passive"))
      (node (ref "RN1") (pin "2") (pinfunction "2_2") (pintype "passive"))
    )
    (net (code "23") (name "/TRIM_BG<3>") (class "Default")
      (node (ref "BG") (pin "7") (pinfunction "COM_4_7") (pintype "passive"))
      (node (ref "IADC_IC") (pin "40") (pinfunction "TRIM_BG<3>_40") (pintype "passive"))
      (node (ref "RN1") (pin "5") (pinfunction "5_5") (pintype "passive"))
    )
    (net (code "24") (name "/TRIM_BG<4>") (class "Default")
      (node (ref "BG") (pin "11") (pinfunction "COM_6_11") (pintype "passive"))
      (node (ref "IADC_IC") (pin "38") (pinfunction "TRIM_BG<4>_38") (pintype "passive"))
      (node (ref "RN1") (pin "3") (pinfunction "3_3") (pintype "passive"))
    )
    (net (code "25") (name "/TRIM_BG<5>") (class "Default")
      (node (ref "BG") (pin "3") (pinfunction "COM_2_3") (pintype "passive"))
      (node (ref "IADC_IC") (pin "42") (pinfunction "TRIM_BG<5>_42") (pintype "passive"))
      (node (ref "RN1") (pin "7") (pinfunction "7_7") (pintype "passive"))
    )
    (net (code "26") (name "/TRIM_CAP<0>") (class "Default")
      (node (ref "CAP") (pin "1") (pinfunction "S1A_1") (pintype "passive"))
      (node (ref "IADC_IC") (pin "8") (pinfunction "TRIM_CAP<0>_8") (pintype "passive"))
      (node (ref "R_T_CAP0") (pin "2") (pinfunction "2_2") (pintype "passive"))
    )
    (net (code "27") (name "/TRIM_CAP<1>") (class "Default")
      (node (ref "CAP") (pin "2") (pinfunction "S2A_2") (pintype "passive"))
      (node (ref "IADC_IC") (pin "7") (pinfunction "TRIM_CAP<1>_7") (pintype "passive"))
      (node (ref "R_T_CAP1") (pin "2") (pinfunction "2_2") (pintype "passive"))
    )
    (net (code "28") (name "/TRIM_DE<0>") (class "Default")
      (node (ref "DE") (pin "2") (pinfunction "S2A_2") (pintype "passive"))
      (node (ref "IADC_IC") (pin "31") (pinfunction "TRIM_DE<0>_31") (pintype "passive"))
      (node (ref "R_T_DE0") (pin "2") (pinfunction "2_2") (pintype "passive"))
    )
    (net (code "29") (name "/TRIM_DE<1>") (class "Default")
      (node (ref "DE") (pin "1") (pinfunction "S1A_1") (pintype "passive"))
      (node (ref "IADC_IC") (pin "32") (pinfunction "TRIM_DE<1>_32") (pintype "passive"))
      (node (ref "R_T_DE1") (pin "2") (pinfunction "2_2") (pintype "passive"))
    )
    (net (code "30") (name "/VDD_2V8") (class "Default")
      (node (ref "L_2V8") (pin "5") (pinfunction "VOUT_5") (pintype "passive"))
      (node (ref "P5") (pin "1") (pinfunction "1_1") (pintype "passive"))
    )
    (net (code "31") (name "/VDD_2V8_BG") (class "Default")
      (node (ref "C28") (pin "1") (pinfunction "1_1") (pintype "passive"))
      (node (ref "C29") (pin "1") (pinfunction "1_1") (pintype "passive"))
      (node (ref "C30") (pin "1") (pinfunction "1_1") (pintype "passive"))
      (node (ref "IADC_IC") (pin "43") (pinfunction "VDD_2V8_BG_43") (pintype "passive"))
      (node (ref "L_BG") (pin "5") (pinfunction "VOUT_5") (pintype "passive"))
    )
    (net (code "32") (name "/VDD_2V8_IC") (class "Default")
      (node (ref "C10") (pin "1") (pinfunction "1_1") (pintype "passive"))
      (node (ref "C11") (pin "1") (pinfunction "1_1") (pintype "passive"))
      (node (ref "C12") (pin "1") (pinfunction "1_1") (pintype "passive"))
      (node (ref "IADC_IC") (pin "12") (pinfunction "VDD_2V8_2_12") (pintype "passive"))
      (node (ref "IADC_IC") (pin "33") (pinfunction "VDD_2V8_1_33") (pintype "passive"))
      (node (ref "IADC_IC") (pin "6") (pinfunction "VDD_2V8_0_6") (pintype "passive"))
      (node (ref "P5") (pin "2") (pinfunction "2_2") (pintype "passive"))
    )
    (net (code "33") (name "/VDD_2V8_OP") (class "Default")
      (node (ref "L_OP") (pin "5") (pinfunction "VOUT_5") (pintype "passive"))
      (node (ref "P2") (pin "1") (pinfunction "1_1") (pintype "passive"))
      (node (ref "P3") (pin "1") (pinfunction "1_1") (pintype "passive"))
      (node (ref "P4") (pin "1") (pinfunction "1_1") (pintype "passive"))
    )
    (net (code "34") (name "/VDD_2V8_OP1") (class "Default")
      (node (ref "C19") (pin "1") (pinfunction "1_1") (pintype "passive"))
      (node (ref "C20") (pin "1") (pinfunction "1_1") (pintype "passive"))
      (node (ref "C21") (pin "1") (pinfunction "1_1") (pintype "passive"))
      (node (ref "IADC_IC") (pin "48") (pinfunction "VDD_2V8_OP1_48") (pintype "passive"))
      (node (ref "P2") (pin "2") (pinfunction "2_2") (pintype "passive"))
    )
    (net (code "35") (name "/VDD_2V8_OP2") (class "Default")
      (node (ref "C16") (pin "1") (pinfunction "1_1") (pintype "passive"))
      (node (ref "C17") (pin "1") (pinfunction "1_1") (pintype "passive"))
      (node (ref "C18") (pin "1") (pinfunction "1_1") (pintype "passive"))
      (node (ref "IADC_IC") (pin "47") (pinfunction "VDD_2V8_OP2_47") (pintype "passive"))
      (node (ref "P3") (pin "2") (pinfunction "2_2") (pintype "passive"))
    )
    (net (code "36") (name "/VDD_2V8_OP3") (class "Default")
      (node (ref "C13") (pin "1") (pinfunction "1_1") (pintype "passive"))
      (node (ref "C14") (pin "1") (pinfunction "1_1") (pintype "passive"))
      (node (ref "C15") (pin "1") (pinfunction "1_1") (pintype "passive"))
      (node (ref "IADC_IC") (pin "46") (pinfunction "VDD_2V8_OP3_46") (pintype "passive"))
      (node (ref "P4") (pin "2") (pinfunction "2_2") (pintype "passive"))
    )
    (net (code "37") (name "/VDD_2V8_SW") (class "Default")
      (node (ref "BG") (pin "10") (pinfunction "NO_5_10") (pintype "passive"))
      (node (ref "BG") (pin "12") (pinfunction "NO_6_12") (pintype "passive"))
      (node (ref "BG") (pin "14") (pinfunction "NO_7_14") (pintype "passive"))
      (node (ref "BG") (pin "2") (pinfunction "NO_1_2") (pintype "passive"))
      (node (ref "BG") (pin "4") (pinfunction "NO_2_4") (pintype "passive"))
      (node (ref "BG") (pin "6") (pinfunction "NO_3_6") (pintype "passive"))
      (node (ref "BG") (pin "8") (pinfunction "NO_4_8") (pintype "passive"))
      (node (ref "BUF") (pin "3") (pinfunction "S2B_3") (pintype "passive"))
      (node (ref "BUF") (pin "4") (pinfunction "S1B_4") (pintype "passive"))
      (node (ref "C40") (pin "1") (pinfunction "1_1") (pintype "passive"))
      (node (ref "C41") (pin "1") (pinfunction "1_1") (pintype "passive"))
      (node (ref "C42") (pin "1") (pinfunction "1_1") (pintype "passive"))
      (node (ref "CAP") (pin "3") (pinfunction "S2B_3") (pintype "passive"))
      (node (ref "CAP") (pin "4") (pinfunction "S1B_4") (pintype "passive"))
      (node (ref "DE") (pin "3") (pinfunction "S2B_3") (pintype "passive"))
      (node (ref "DE") (pin "4") (pinfunction "S1B_4") (pintype "passive"))
      (node (ref "L_SW") (pin "5") (pinfunction "VOUT_5") (pintype "passive"))
      (node (ref "U7") (pin "10") (pinfunction "OE_10") (pintype "input"))
      (node (ref "U7") (pin "2") (pinfunction "VCCA_2") (pintype "power_in"))
    )
    (net (code "38") (name "/VDD_IO") (class "Default")
      (node (ref "L_IO") (pin "5") (pinfunction "VOUT_5") (pintype "passive"))
      (node (ref "P8") (pin "1") (pinfunction "1_1") (pintype "passive"))
    )
    (net (code "39") (name "/VDD_IO_IC") (class "Default")
      (node (ref "C25") (pin "1") (pinfunction "1_1") (pintype "passive"))
      (node (ref "C26") (pin "1") (pinfunction "1_1") (pintype "passive"))
      (node (ref "C27") (pin "1") (pinfunction "1_1") (pintype "passive"))
      (node (ref "C4") (pin "1") (pinfunction "1_1") (pintype "passive"))
      (node (ref "C5") (pin "1") (pinfunction "1_1") (pintype "passive"))
      (node (ref "C6") (pin "1") (pinfunction "1_1") (pintype "passive"))
      (node (ref "IADC_IC") (pin "10") (pinfunction "VDD_IO1_10") (pintype "passive"))
      (node (ref "IADC_IC") (pin "15") (pinfunction "VDD_IO0_15") (pintype "passive"))
      (node (ref "P8") (pin "2") (pinfunction "2_2") (pintype "passive"))
    )
    (net (code "40") (name "/VGND_O") (class "Default")
      (node (ref "FAVSS0") (pin "1") (pinfunction "1_1") (pintype "passive"))
      (node (ref "FAVSS1") (pin "1") (pinfunction "1_1") (pintype "passive"))
      (node (ref "FDVSS") (pin "1") (pinfunction "1_1") (pintype "passive"))
      (node (ref "FVSS") (pin "1") (pinfunction "1_1") (pintype "passive"))
      (node (ref "FVSS_IO0") (pin "1") (pinfunction "1_1") (pintype "passive"))
      (node (ref "P10") (pin "7") (pinfunction "7_7") (pintype "passive"))
    )
    (net (code "41") (name "/VIN") (class "Default")
      (node (ref "IADC_IC") (pin "4") (pinfunction "VIN_4") (pintype "passive"))
      (node (ref "J1") (pin "3") (pinfunction "3_3") (pintype "passive"))
      (node (ref "P1") (pin "1") (pinfunction "1_1") (pintype "passive"))
    )
    (net (code "42") (name "/VIP") (class "Default")
      (node (ref "IADC_IC") (pin "3") (pinfunction "VIP_3") (pintype "passive"))
      (node (ref "J1") (pin "2") (pinfunction "2_2") (pintype "passive"))
      (node (ref "P1") (pin "2") (pinfunction "2_2") (pintype "passive"))
    )
    (net (code "43") (name "/VO") (class "Default")
      (node (ref "IADC_IC") (pin "25") (pinfunction "VO_25") (pintype "passive"))
      (node (ref "U7") (pin "3") (pinfunction "A2_3") (pintype "bidirectional"))
    )
    (net (code "44") (name "/VO_INT1N") (class "Default")
      (node (ref "ESD_OUT") (pin "1") (pinfunction "I/O_1_1") (pintype "passive"))
      (node (ref "IADC_IC") (pin "16") (pinfunction "VO_INT1N_16") (pintype "passive"))
      (node (ref "P11") (pin "2") (pinfunction "2_2") (pintype "passive"))
    )
    (net (code "45") (name "/VO_INT1P") (class "Default")
      (node (ref "ESD_OUT") (pin "8") (pinfunction "I/O_6_8") (pintype "passive"))
      (node (ref "IADC_IC") (pin "21") (pinfunction "VO_INT1P_21") (pintype "passive"))
      (node (ref "P11") (pin "7") (pinfunction "7_7") (pintype "passive"))
    )
    (net (code "46") (name "/VO_INT2N") (class "Default")
      (node (ref "ESD_OUT") (pin "2") (pinfunction "I/O_2_2") (pintype "passive"))
      (node (ref "IADC_IC") (pin "17") (pinfunction "VO_INT2N_17") (pintype "passive"))
      (node (ref "P11") (pin "3") (pinfunction "3_3") (pintype "passive"))
    )
    (net (code "47") (name "/VO_INT2P") (class "Default")
      (node (ref "ESD_OUT") (pin "7") (pinfunction "I/O_5_7") (pintype "passive"))
      (node (ref "IADC_IC") (pin "20") (pinfunction "VO_INT2P_20") (pintype "passive"))
      (node (ref "P11") (pin "6") (pinfunction "6_6") (pintype "passive"))
    )
    (net (code "48") (name "/VO_INT3N") (class "Default")
      (node (ref "ESD_OUT") (pin "4") (pinfunction "I/O_3_4") (pintype "passive"))
      (node (ref "IADC_IC") (pin "18") (pinfunction "VO_INT3N_18") (pintype "passive"))
      (node (ref "P11") (pin "4") (pinfunction "4_4") (pintype "passive"))
    )
    (net (code "49") (name "/VO_INT3P") (class "Default")
      (node (ref "ESD_OUT") (pin "5") (pinfunction "I/O_4_5") (pintype "passive"))
      (node (ref "IADC_IC") (pin "19") (pinfunction "VO_INT3P_19") (pintype "passive"))
      (node (ref "P11") (pin "5") (pinfunction "5_5") (pintype "passive"))
    )
    (net (code "50") (name "/VO_OUT") (class "Default")
      (node (ref "P12") (pin "4") (pinfunction "4_4") (pintype "passive"))
      (node (ref "U7") (pin "18") (pinfunction "B2_18") (pintype "bidirectional"))
    )
    (net (code "51") (name "/VREF2V49") (class "Default")
      (node (ref "R11") (pin "1") (pinfunction "1_1") (pintype "passive"))
      (node (ref "R12") (pin "1") (pinfunction "1_1") (pintype "passive"))
      (node (ref "R14") (pin "2") (pinfunction "2_2") (pintype "passive"))
      (node (ref "R2") (pin "1") (pinfunction "1_1") (pintype "passive"))
      (node (ref "U4") (pin "8") (pinfunction "CATHODE_8") (pintype "passive"))
      (node (ref "VR_P_5K") (pin "1") (pinfunction "CCW_1") (pintype "passive"))
    )
    (net (code "52") (name "/VREFN") (class "Default")
      (node (ref "C38") (pin "1") (pinfunction "1_1") (pintype "passive"))
      (node (ref "IADC_IC") (pin "2") (pinfunction "VREFN_2") (pintype "passive"))
      (node (ref "TP3") (pin "1") (pinfunction "TP_1") (pintype "passive"))
      (node (ref "U1") (pin "1") (pinfunction "OUT_A_1") (pintype "output"))
      (node (ref "U1") (pin "2") (pinfunction "IN_A-_2") (pintype "input"))
    )
    (net (code "53") (name "/VREFP") (class "Default")
      (node (ref "C34") (pin "1") (pinfunction "1_1") (pintype "passive"))
      (node (ref "IADC_IC") (pin "1") (pinfunction "VREFP_1") (pintype "passive"))
      (node (ref "TP5") (pin "1") (pinfunction "TP_1") (pintype "passive"))
      (node (ref "U3") (pin "1") (pinfunction "OUT_A_1") (pintype "output"))
      (node (ref "U3") (pin "2") (pinfunction "IN_A-_2") (pintype "input"))
    )
    (net (code "54") (name "/VREF_1V4") (class "Default")
      (node (ref "C36") (pin "1") (pinfunction "1_1") (pintype "passive"))
      (node (ref "IADC_IC") (pin "9") (pinfunction "VREF_1V4_9") (pintype "passive"))
      (node (ref "TP4") (pin "1") (pinfunction "TP_1") (pintype "passive"))
      (node (ref "U5") (pin "1") (pinfunction "OUT_A_1") (pintype "output"))
      (node (ref "U5") (pin "2") (pinfunction "IN_A-_2") (pintype "input"))
    )
    (net (code "55") (name "AVSS0") (class "Default")
      (node (ref "C13") (pin "2") (pinfunction "2_2") (pintype "passive"))
      (node (ref "C14") (pin "2") (pinfunction "2_2") (pintype "passive"))
      (node (ref "C15") (pin "2") (pinfunction "2_2") (pintype "passive"))
      (node (ref "C16") (pin "2") (pinfunction "2_2") (pintype "passive"))
      (node (ref "C17") (pin "2") (pinfunction "2_2") (pintype "passive"))
      (node (ref "C18") (pin "2") (pinfunction "2_2") (pintype "passive"))
      (node (ref "C19") (pin "2") (pinfunction "2_2") (pintype "passive"))
      (node (ref "C20") (pin "2") (pinfunction "2_2") (pintype "passive"))
      (node (ref "C21") (pin "2") (pinfunction "2_2") (pintype "passive"))
      (node (ref "FAVSS0") (pin "2") (pinfunction "2_2") (pintype "passive"))
      (node (ref "IADC_IC") (pin "5") (pinfunction "AVSS0_5") (pintype "passive"))
      (node (ref "L_OP") (pin "2") (pinfunction "GND_2") (pintype "passive"))
      (node (ref "L_OP") (pin "4") (pinfunction "NC_4") (pintype "passive"))
    )
    (net (code "56") (name "AVSS1") (class "Default")
      (node (ref "C28") (pin "2") (pinfunction "2_2") (pintype "passive"))
      (node (ref "C29") (pin "2") (pinfunction "2_2") (pintype "passive"))
      (node (ref "C30") (pin "2") (pinfunction "2_2") (pintype "passive"))
      (node (ref "FAVSS1") (pin "2") (pinfunction "2_2") (pintype "passive"))
      (node (ref "IADC_IC") (pin "13") (pinfunction "AVSS1_13") (pintype "passive"))
      (node (ref "L_BG") (pin "2") (pinfunction "GND_2") (pintype "passive"))
      (node (ref "L_BG") (pin "4") (pinfunction "NC_4") (pintype "passive"))
    )
    (net (code "57") (name "DVSS") (class "Default")
      (node (ref "C10") (pin "2") (pinfunction "2_2") (pintype "passive"))
      (node (ref "C11") (pin "2") (pinfunction "2_2") (pintype "passive"))
      (node (ref "C12") (pin "2") (pinfunction "2_2") (pintype "passive"))
      (node (ref "FDVSS") (pin "2") (pinfunction "2_2") (pintype "passive"))
      (node (ref "IADC_IC") (pin "34") (pinfunction "DVSS_34") (pintype "passive"))
      (node (ref "L_2V8") (pin "2") (pinfunction "GND_2") (pintype "passive"))
      (node (ref "L_2V8") (pin "4") (pinfunction "NC_4") (pintype "passive"))
    )
    (net (code "58") (name "Net-(L_2V8-EN)") (class "Default")
      (node (ref "L_2V8") (pin "3") (pinfunction "EN_3") (pintype "passive"))
      (node (ref "R1") (pin "2") (pinfunction "2_2") (pintype "passive"))
    )
    (net (code "59") (name "Net-(L_BG-EN)") (class "Default")
      (node (ref "L_BG") (pin "3") (pinfunction "EN_3") (pintype "passive"))
      (node (ref "R7") (pin "2") (pinfunction "2_2") (pintype "passive"))
    )
    (net (code "60") (name "Net-(L_IO-EN)") (class "Default")
      (node (ref "L_IO") (pin "3") (pinfunction "EN_3") (pintype "passive"))
      (node (ref "R8") (pin "2") (pinfunction "2_2") (pintype "passive"))
    )
    (net (code "61") (name "Net-(L_OP-EN)") (class "Default")
      (node (ref "L_OP") (pin "3") (pinfunction "EN_3") (pintype "passive"))
      (node (ref "R4") (pin "2") (pinfunction "2_2") (pintype "passive"))
    )
    (net (code "62") (name "Net-(L_SW-EN)") (class "Default")
      (node (ref "L_SW") (pin "3") (pinfunction "EN_3") (pintype "passive"))
      (node (ref "R9") (pin "2") (pinfunction "2_2") (pintype "passive"))
    )
    (net (code "63") (name "Net-(TP1-TP)") (class "Default")
      (node (ref "C31") (pin "1") (pinfunction "1_1") (pintype "passive"))
      (node (ref "C32") (pin "1") (pinfunction "1_1") (pintype "passive"))
      (node (ref "R10") (pin "1") (pinfunction "1_1") (pintype "passive"))
      (node (ref "R3") (pin "1") (pinfunction "1_1") (pintype "passive"))
      (node (ref "TP1") (pin "1") (pinfunction "TP_1") (pintype "passive"))
      (node (ref "U2") (pin "8") (pinfunction "CATHODE_8") (pintype "passive"))
      (node (ref "VR_IB_10K") (pin "1") (pinfunction "CCW_1") (pintype "passive"))
    )
    (net (code "64") (name "Net-(TP2-TP)") (class "Default")
      (node (ref "R5") (pin "2") (pinfunction "2_2") (pintype "passive"))
      (node (ref "TP2") (pin "1") (pinfunction "TP_1") (pintype "passive"))
      (node (ref "U2") (pin "4") (pinfunction "ANODE_4") (pintype "passive"))
      (node (ref "U6") (pin "1") (pinfunction "OUT_A_1") (pintype "output"))
      (node (ref "U6") (pin "2") (pinfunction "IN_A-_2") (pintype "input"))
    )
    (net (code "65") (name "Net-(U1A-IN_A+)") (class "Default")
      (node (ref "C37") (pin "1") (pinfunction "1_1") (pintype "passive"))
      (node (ref "U1") (pin "3") (pinfunction "IN_A+_3") (pintype "input"))
      (node (ref "VR_N_5K") (pin "2") (pinfunction "WIPER_2") (pintype "passive"))
    )
    (net (code "66") (name "Net-(U2A-ADJ)") (class "Default")
      (node (ref "R3") (pin "2") (pinfunction "2_2") (pintype "passive"))
      (node (ref "R5") (pin "1") (pinfunction "1_1") (pintype "passive"))
      (node (ref "U2") (pin "5") (pinfunction "ADJ_5") (pintype "input"))
    )
    (net (code "67") (name "Net-(U3A-IN_A+)") (class "Default")
      (node (ref "C33") (pin "1") (pinfunction "1_1") (pintype "passive"))
      (node (ref "U3") (pin "3") (pinfunction "IN_A+_3") (pintype "input"))
      (node (ref "VR_P_5K") (pin "2") (pinfunction "WIPER_2") (pintype "passive"))
    )
    (net (code "68") (name "Net-(U4A-ADJ)") (class "Default")
      (node (ref "R14") (pin "1") (pinfunction "1_1") (pintype "passive"))
      (node (ref "R20") (pin "1") (pinfunction "1_1") (pintype "passive"))
      (node (ref "U4") (pin "5") (pinfunction "ADJ_5") (pintype "input"))
    )
    (net (code "69") (name "Net-(U5A-IN_A+)") (class "Default")
      (node (ref "C35") (pin "1") (pinfunction "1_1") (pintype "passive"))
      (node (ref "U5") (pin "3") (pinfunction "IN_A+_3") (pintype "input"))
      (node (ref "VR_1V4_5K") (pin "2") (pinfunction "WIPER_2") (pintype "passive"))
    )
    (net (code "70") (name "Net-(U6A-IN_A+)") (class "Default")
      (node (ref "C31") (pin "2") (pinfunction "2_2") (pintype "passive"))
      (node (ref "C32") (pin "2") (pinfunction "2_2") (pintype "passive"))
      (node (ref "C39") (pin "1") (pinfunction "1_1") (pintype "passive"))
      (node (ref "P16") (pin "1") (pinfunction "1_1") (pintype "passive"))
      (node (ref "R6") (pin "1") (pinfunction "1_1") (pintype "passive"))
      (node (ref "U6") (pin "3") (pinfunction "IN_A+_3") (pintype "input"))
    )
    (net (code "71") (name "Net-(VR_1V4_5K-CCW)") (class "Default")
      (node (ref "R11") (pin "2") (pinfunction "2_2") (pintype "passive"))
      (node (ref "VR_1V4_5K") (pin "1") (pinfunction "CCW_1") (pintype "passive"))
    )
    (net (code "72") (name "Net-(VR_1V4_5K-CW)") (class "Default")
      (node (ref "R16") (pin "1") (pinfunction "1_1") (pintype "passive"))
      (node (ref "VR_1V4_5K") (pin "3") (pinfunction "CW_3") (pintype "passive"))
    )
    (net (code "73") (name "Net-(VR_IB_10K-CW)") (class "Default")
      (node (ref "R6") (pin "2") (pinfunction "2_2") (pintype "passive"))
      (node (ref "VR_IB_10K") (pin "2") (pinfunction "WIPER_2") (pintype "passive"))
      (node (ref "VR_IB_10K") (pin "3") (pinfunction "CW_3") (pintype "passive"))
    )
    (net (code "74") (name "Net-(VR_N_5K-CCW)") (class "Default")
      (node (ref "R12") (pin "2") (pinfunction "2_2") (pintype "passive"))
      (node (ref "VR_N_5K") (pin "1") (pinfunction "CCW_1") (pintype "passive"))
    )
    (net (code "75") (name "Net-(VR_N_5K-CW)") (class "Default")
      (node (ref "R17") (pin "1") (pinfunction "1_1") (pintype "passive"))
      (node (ref "VR_N_5K") (pin "3") (pinfunction "CW_3") (pintype "passive"))
    )
    (net (code "76") (name "Net-(VR_P_5K-CW)") (class "Default")
      (node (ref "R15") (pin "1") (pinfunction "1_1") (pintype "passive"))
      (node (ref "VR_P_5K") (pin "3") (pinfunction "CW_3") (pintype "passive"))
    )
    (net (code "77") (name "PCB_VDD") (class "Default")
      (node (ref "C1") (pin "1") (pinfunction "1_1") (pintype "passive"))
      (node (ref "C2") (pin "1") (pinfunction "1_1") (pintype "passive"))
      (node (ref "C3") (pin "1") (pinfunction "1_1") (pintype "passive"))
      (node (ref "L_2V8") (pin "1") (pinfunction "VIN_1") (pintype "passive"))
      (node (ref "L_BG") (pin "1") (pinfunction "VIN_1") (pintype "passive"))
      (node (ref "L_IO") (pin "1") (pinfunction "VIN_1") (pintype "passive"))
      (node (ref "L_OP") (pin "1") (pinfunction "VIN_1") (pintype "passive"))
      (node (ref "L_SW") (pin "1") (pinfunction "VIN_1") (pintype "passive"))
      (node (ref "P10") (pin "6") (pinfunction "6_6") (pintype "passive"))
      (node (ref "P13") (pin "1") (pinfunction "1_1") (pintype "passive"))
      (node (ref "P14") (pin "1") (pinfunction "1_1") (pintype "passive"))
      (node (ref "R1") (pin "1") (pinfunction "1_1") (pintype "passive"))
      (node (ref "R2") (pin "2") (pinfunction "2_2") (pintype "passive"))
      (node (ref "R4") (pin "1") (pinfunction "1_1") (pintype "passive"))
      (node (ref "R7") (pin "1") (pinfunction "1_1") (pintype "passive"))
      (node (ref "R8") (pin "1") (pinfunction "1_1") (pintype "passive"))
      (node (ref "R9") (pin "1") (pinfunction "1_1") (pintype "passive"))
      (node (ref "U1") (pin "8") (pinfunction "V+_8") (pintype "power_in"))
      (node (ref "U3") (pin "8") (pinfunction "V+_8") (pintype "power_in"))
      (node (ref "U5") (pin "8") (pinfunction "V+_8") (pintype "power_in"))
      (node (ref "U7") (pin "19") (pinfunction "VCCB_19") (pintype "power_in"))
    )
    (net (code "78") (name "PCB_VDD_5V") (class "Default")
      (node (ref "C43") (pin "1") (pinfunction "1_1") (pintype "passive"))
      (node (ref "C44") (pin "1") (pinfunction "1_1") (pintype "passive"))
      (node (ref "C45") (pin "1") (pinfunction "1_1") (pintype "passive"))
      (node (ref "P17") (pin "1") (pinfunction "1_1") (pintype "passive"))
      (node (ref "P18") (pin "1") (pinfunction "1_1") (pintype "passive"))
      (node (ref "R10") (pin "2") (pinfunction "2_2") (pintype "passive"))
      (node (ref "U6") (pin "8") (pinfunction "V+_8") (pintype "power_in"))
    )
    (net (code "79") (name "VSS") (class "Default")
      (node (ref "C1") (pin "2") (pinfunction "2_2") (pintype "passive"))
      (node (ref "C2") (pin "2") (pinfunction "2_2") (pintype "passive"))
      (node (ref "C3") (pin "2") (pinfunction "2_2") (pintype "passive"))
      (node (ref "C33") (pin "2") (pinfunction "2_2") (pintype "passive"))
      (node (ref "C34") (pin "2") (pinfunction "2_2") (pintype "passive"))
      (node (ref "C35") (pin "2") (pinfunction "2_2") (pintype "passive"))
      (node (ref "C36") (pin "2") (pinfunction "2_2") (pintype "passive"))
      (node (ref "C37") (pin "2") (pinfunction "2_2") (pintype "passive"))
      (node (ref "C38") (pin "2") (pinfunction "2_2") (pintype "passive"))
      (node (ref "C39") (pin "2") (pinfunction "2_2") (pintype "passive"))
      (node (ref "C40") (pin "2") (pinfunction "2_2") (pintype "passive"))
      (node (ref "C41") (pin "2") (pinfunction "2_2") (pintype "passive"))
      (node (ref "C42") (pin "2") (pinfunction "2_2") (pintype "passive"))
      (node (ref "C43") (pin "2") (pinfunction "2_2") (pintype "passive"))
      (node (ref "C44") (pin "2") (pinfunction "2_2") (pintype "passive"))
      (node (ref "C45") (pin "2") (pinfunction "2_2") (pintype "passive"))
      (node (ref "CK_IN") (pin "2") (pinfunction "MNT_1_2") (pintype "passive"))
      (node (ref "CK_IN") (pin "3") (pinfunction "MNT_2_3") (pintype "passive"))
      (node (ref "CK_IN") (pin "4") (pinfunction "MNT_3_4") (pintype "passive"))
      (node (ref "CK_IN") (pin "5") (pinfunction "MNT_4_5") (pintype "passive"))
      (node (ref "ESD_CK") (pin "2") (pinfunction "K2_2") (pintype "passive"))
      (node (ref "ESD_OUT") (pin "10") (pinfunction "GND_4_10") (pintype "passive"))
      (node (ref "ESD_OUT") (pin "3") (pinfunction "GND_1_3") (pintype "passive"))
      (node (ref "ESD_OUT") (pin "6") (pinfunction "GND_2_6") (pintype "passive"))
      (node (ref "ESD_OUT") (pin "9") (pinfunction "GND_3_9") (pintype "passive"))
      (node (ref "FVSS") (pin "2") (pinfunction "2_2") (pintype "passive"))
      (node (ref "J1") (pin "1") (pinfunction "1_1") (pintype "passive"))
      (node (ref "L_SW") (pin "2") (pinfunction "GND_2") (pintype "passive"))
      (node (ref "L_SW") (pin "4") (pinfunction "NC_4") (pintype "passive"))
      (node (ref "P1") (pin "3") (pinfunction "3_3") (pintype "passive"))
      (node (ref "P10") (pin "5") (pinfunction "5_5") (pintype "passive"))
      (node (ref "P11") (pin "1") (pinfunction "1_1") (pintype "passive"))
      (node (ref "P12") (pin "1") (pinfunction "1_1") (pintype "passive"))
      (node (ref "P13") (pin "2") (pinfunction "2_2") (pintype "passive"))
      (node (ref "P14") (pin "2") (pinfunction "2_2") (pintype "passive"))
      (node (ref "P15") (pin "2") (pinfunction "2_2") (pintype "passive"))
      (node (ref "P17") (pin "2") (pinfunction "2_2") (pintype "passive"))
      (node (ref "P18") (pin "2") (pinfunction "2_2") (pintype "passive"))
      (node (ref "R15") (pin "2") (pinfunction "2_2") (pintype "passive"))
      (node (ref "R16") (pin "2") (pinfunction "2_2") (pintype "passive"))
      (node (ref "R17") (pin "2") (pinfunction "2_2") (pintype "passive"))
      (node (ref "R20") (pin "2") (pinfunction "2_2") (pintype "passive"))
      (node (ref "RN1") (pin "1") (pinfunction "1_1") (pintype "passive"))
      (node (ref "RN1") (pin "10") (pinfunction "10_10") (pintype "passive"))
      (node (ref "RN1") (pin "11") (pinfunction "11_11") (pintype "passive"))
      (node (ref "RN1") (pin "12") (pinfunction "12_12") (pintype "passive"))
      (node (ref "RN1") (pin "13") (pinfunction "13_13") (pintype "passive"))
      (node (ref "RN1") (pin "14") (pinfunction "14_14") (pintype "passive"))
      (node (ref "RN1") (pin "15") (pinfunction "15_15") (pintype "passive"))
      (node (ref "RN1") (pin "16") (pinfunction "16_16") (pintype "passive"))
      (node (ref "RN1") (pin "9") (pinfunction "9_9") (pintype "passive"))
      (node (ref "R_S_BUF0") (pin "1") (pinfunction "1_1") (pintype "passive"))
      (node (ref "R_S_BUF1") (pin "1") (pinfunction "1_1") (pintype "passive"))
      (node (ref "R_T_CAP0") (pin "1") (pinfunction "1_1") (pintype "passive"))
      (node (ref "R_T_CAP1") (pin "1") (pinfunction "1_1") (pintype "passive"))
      (node (ref "R_T_DE0") (pin "1") (pinfunction "1_1") (pintype "passive"))
      (node (ref "R_T_DE1") (pin "1") (pinfunction "1_1") (pintype "passive"))
      (node (ref "U1") (pin "4") (pinfunction "V-_4") (pintype "power_in"))
      (node (ref "U3") (pin "4") (pinfunction "V-_4") (pintype "power_in"))
      (node (ref "U4") (pin "4") (pinfunction "ANODE_4") (pintype "passive"))
      (node (ref "U5") (pin "4") (pinfunction "V-_4") (pintype "power_in"))
      (node (ref "U6") (pin "4") (pinfunction "V-_4") (pintype "power_in"))
      (node (ref "U7") (pin "11") (pinfunction "GND_11") (pintype "power_in"))
    )
    (net (code "80") (name "VSS_IO_IC") (class "Default")
      (node (ref "C25") (pin "2") (pinfunction "2_2") (pintype "passive"))
      (node (ref "C26") (pin "2") (pinfunction "2_2") (pintype "passive"))
      (node (ref "C27") (pin "2") (pinfunction "2_2") (pintype "passive"))
      (node (ref "C4") (pin "2") (pinfunction "2_2") (pintype "passive"))
      (node (ref "C5") (pin "2") (pinfunction "2_2") (pintype "passive"))
      (node (ref "C6") (pin "2") (pinfunction "2_2") (pintype "passive"))
      (node (ref "FVSS_IO0") (pin "2") (pinfunction "2_2") (pintype "passive"))
      (node (ref "IADC_IC") (pin "11") (pinfunction "VSS_IO1_11") (pintype "passive"))
      (node (ref "IADC_IC") (pin "14") (pinfunction "VSS_IO0_14") (pintype "passive"))
      (node (ref "L_IO") (pin "2") (pinfunction "GND_2") (pintype "passive"))
      (node (ref "L_IO") (pin "4") (pinfunction "NC_4") (pintype "passive"))
    )
  )
)
